# MCU_Power_PCB_Rev1.net
KiCad netlist of a schematic drawn in EAGLE
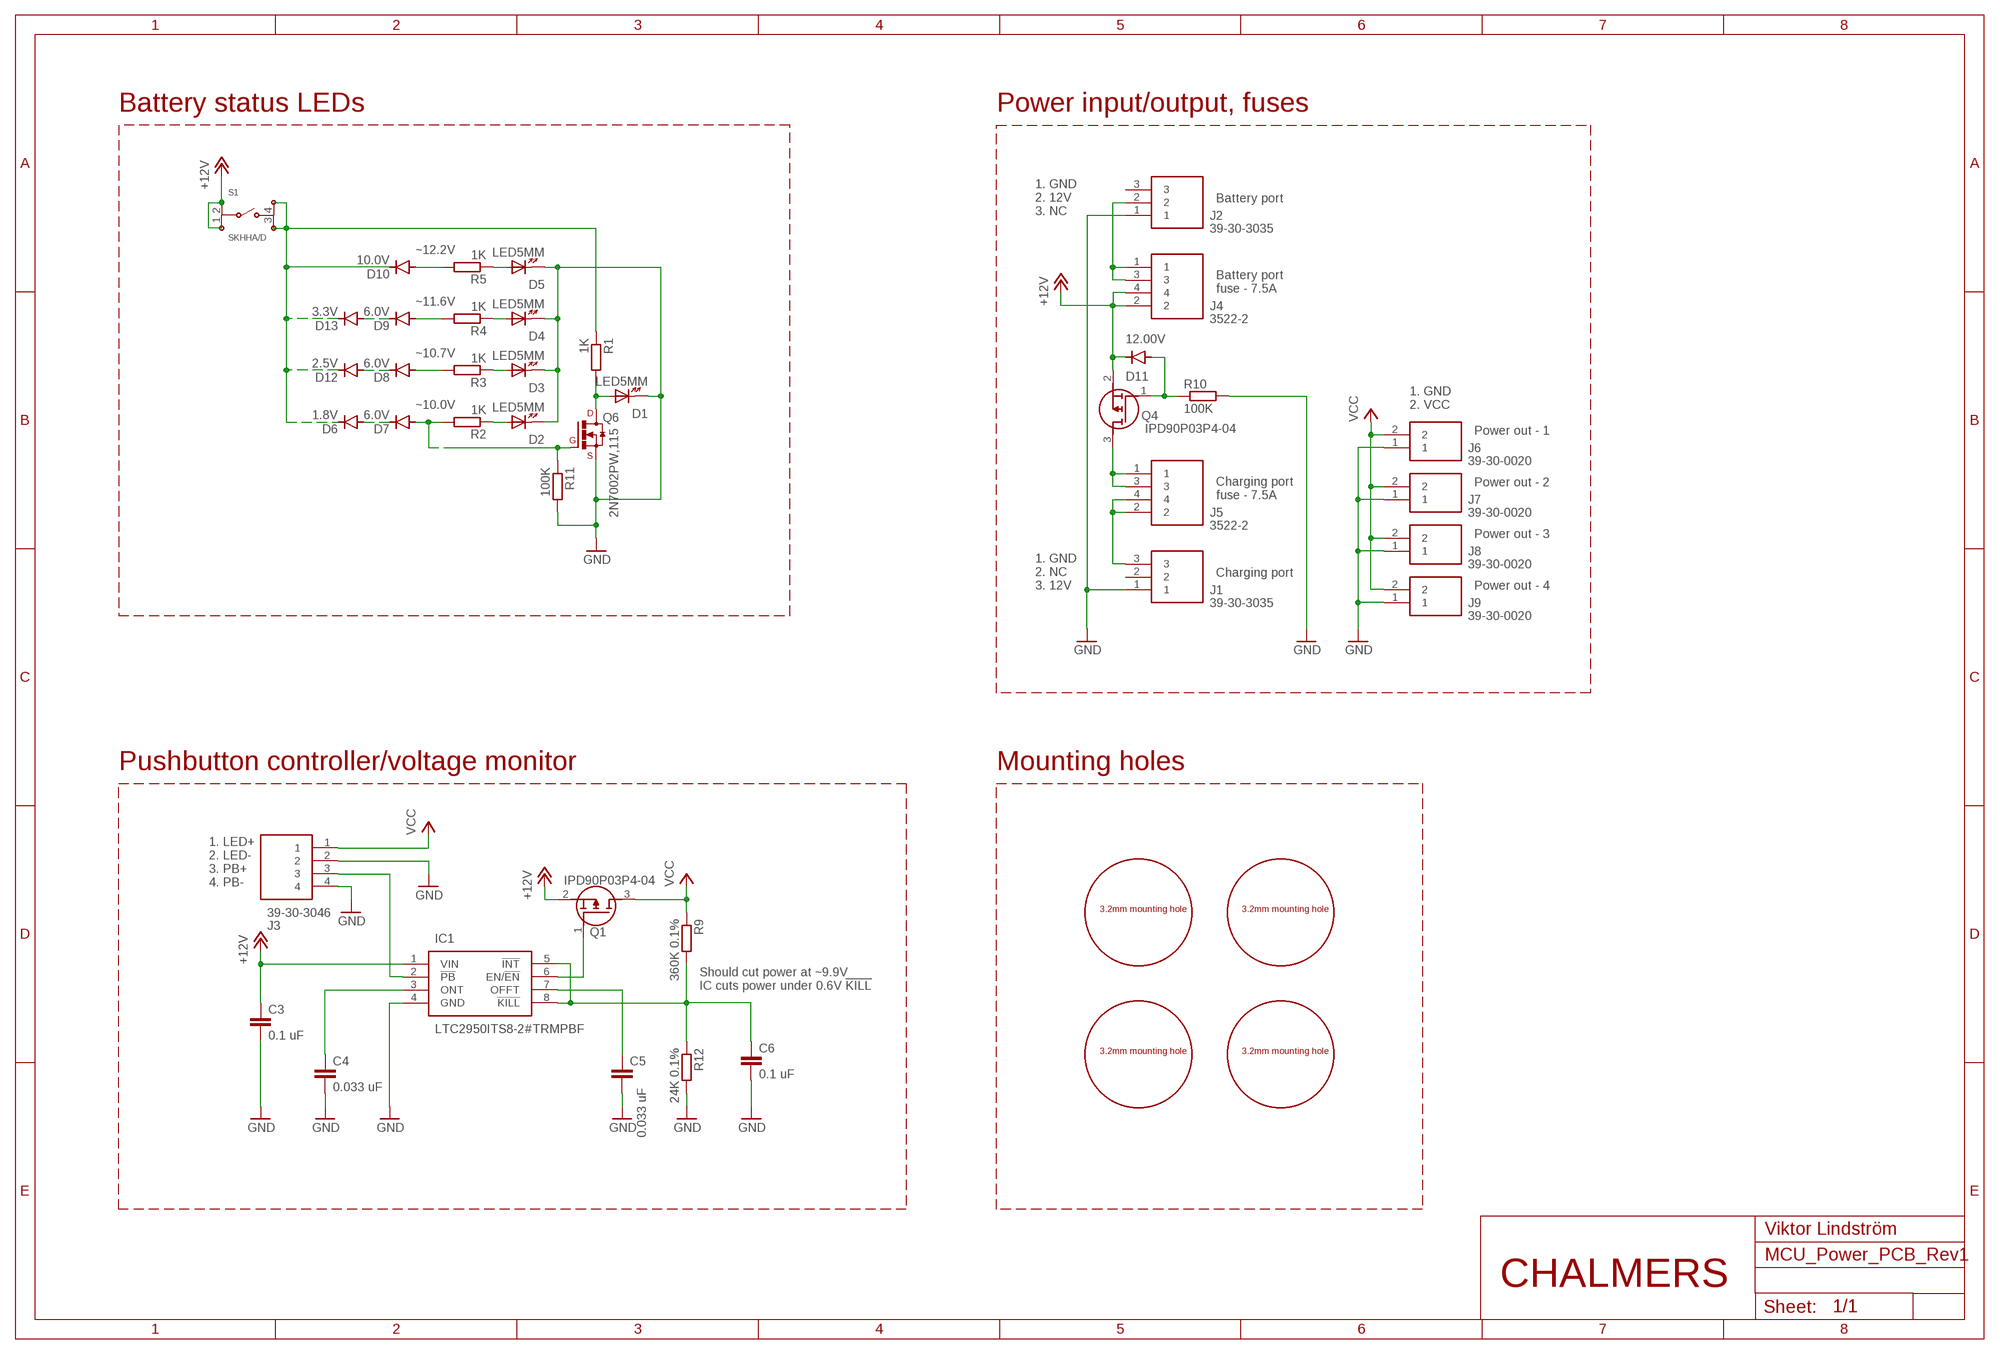
[diagram p0: schematic, sheet 1]

(export (version "E")
  (design (tool "Eeschema 10.0.6"))
  (components
    (comp (ref "C3")
      (value "0.1 uF")
      (footprint "eagle-import:C0603")
      (libsource (lib "eagle-import") (part "C0603"))
    )
    (comp (ref "C4")
      (value "0.033 uF")
      (footprint "eagle-import:C0603")
      (libsource (lib "eagle-import") (part "C0603"))
    )
    (comp (ref "C5")
      (value "0.033 uF")
      (footprint "eagle-import:C0603")
      (libsource (lib "eagle-import") (part "C0603"))
    )
    (comp (ref "C6")
      (value "0.1 uF")
      (footprint "eagle-import:C0603")
      (libsource (lib "eagle-import") (part "C0603"))
    )
    (comp (ref "D1")
      (value "LED5MM")
      (footprint "eagle-import:LED5MM")
      (libsource (lib "eagle-import") (part "LED5MM"))
    )
    (comp (ref "D2")
      (value "LED5MM")
      (footprint "eagle-import:LED5MM")
      (libsource (lib "eagle-import") (part "LED5MM"))
    )
    (comp (ref "D3")
      (value "LED5MM")
      (footprint "eagle-import:LED5MM")
      (libsource (lib "eagle-import") (part "LED5MM"))
    )
    (comp (ref "D4")
      (value "LED5MM")
      (footprint "eagle-import:LED5MM")
      (libsource (lib "eagle-import") (part "LED5MM"))
    )
    (comp (ref "D5")
      (value "LED5MM")
      (footprint "eagle-import:LED5MM")
      (libsource (lib "eagle-import") (part "LED5MM"))
    )
    (comp (ref "D6")
      (value "1.8V")
      (footprint "eagle-import:SOD-123_MINI-SMA")
      (libsource (lib "eagle-import") (part "CGRM400-G1"))
    )
    (comp (ref "D7")
      (value "6.0V")
      (footprint "eagle-import:SOD-123_MINI-SMA")
      (libsource (lib "eagle-import") (part "CGRM400-G1"))
    )
    (comp (ref "D8")
      (value "6.0V")
      (footprint "eagle-import:SOD-123_MINI-SMA")
      (libsource (lib "eagle-import") (part "CGRM400-G1"))
    )
    (comp (ref "D9")
      (value "6.0V")
      (footprint "eagle-import:SOD-123_MINI-SMA")
      (libsource (lib "eagle-import") (part "CGRM400-G1"))
    )
    (comp (ref "D10")
      (value "10.0V")
      (footprint "eagle-import:SOD-123_MINI-SMA")
      (libsource (lib "eagle-import") (part "CGRM400-G1"))
    )
    (comp (ref "D11")
      (value "12.00V")
      (footprint "eagle-import:SOD-123_MINI-SMA")
      (libsource (lib "eagle-import") (part "CGRM400-G1"))
    )
    (comp (ref "D12")
      (value "2.5V")
      (footprint "eagle-import:SOD-123_MINI-SMA")
      (libsource (lib "eagle-import") (part "CGRM400-G1"))
    )
    (comp (ref "D13")
      (value "3.3V")
      (footprint "eagle-import:SOD-123_MINI-SMA")
      (libsource (lib "eagle-import") (part "CGRM400-G1"))
    )
    (comp (ref "HOLE1")
      (value "M3_MOUNTING_HOLE")
      (footprint "eagle-import:M3_MOUNTING_HOLE")
      (libsource (lib "eagle-import") (part "M3_MOUNTING_HOLE"))
    )
    (comp (ref "HOLE2")
      (value "M3_MOUNTING_HOLE")
      (footprint "eagle-import:M3_MOUNTING_HOLE")
      (libsource (lib "eagle-import") (part "M3_MOUNTING_HOLE"))
    )
    (comp (ref "HOLE3")
      (value "M3_MOUNTING_HOLE")
      (footprint "eagle-import:M3_MOUNTING_HOLE")
      (libsource (lib "eagle-import") (part "M3_MOUNTING_HOLE"))
    )
    (comp (ref "HOLE4")
      (value "M3_MOUNTING_HOLE")
      (footprint "eagle-import:M3_MOUNTING_HOLE")
      (libsource (lib "eagle-import") (part "M3_MOUNTING_HOLE"))
    )
    (comp (ref "IC1")
      (value "LTC2950ITS8-2#TRMPBF")
      (footprint "eagle-import:SOT65P280X100-8N")
      (fields (field (name "RS_PART_NUMBER") "8225976P"))
      (libsource (lib "eagle-import") (part "LTC2950ITS8-2#TRMPBF"))
    )
    (comp (ref "J1")
      (value "39-30-3035")
      (footprint "eagle-import:39303035")
      (fields (field (name "RS_PART_NUMBER") "6705849P"))
      (libsource (lib "eagle-import") (part "39-30-3035"))
    )
    (comp (ref "J2")
      (value "39-30-3035")
      (footprint "eagle-import:39303035")
      (fields (field (name "RS_PART_NUMBER") "6705849P"))
      (libsource (lib "eagle-import") (part "39-30-3035"))
    )
    (comp (ref "J3")
      (value "39-30-3046")
      (footprint "eagle-import:39303046")
      (fields (field (name "RS_PART_NUMBER") "6705859P"))
      (libsource (lib "eagle-import") (part "39-30-3046"))
    )
    (comp (ref "J4")
      (value "3522-2")
      (footprint "eagle-import:35222")
      (fields (field (name "RS_PART_NUMBER") "1676068"))
      (libsource (lib "eagle-import") (part "3522-2"))
    )
    (comp (ref "J5")
      (value "3522-2")
      (footprint "eagle-import:35222")
      (fields (field (name "RS_PART_NUMBER") "1676068"))
      (libsource (lib "eagle-import") (part "3522-2"))
    )
    (comp (ref "J6")
      (value "39-30-0020")
      (footprint "eagle-import:39-30-1020_1")
      (fields (field (name "RS_PART_NUMBER") "6705708P"))
      (libsource (lib "eagle-import") (part "39-30-0020"))
    )
    (comp (ref "J7")
      (value "39-30-0020")
      (footprint "eagle-import:39-30-1020_1")
      (fields (field (name "RS_PART_NUMBER") "6705708P"))
      (libsource (lib "eagle-import") (part "39-30-0020"))
    )
    (comp (ref "J8")
      (value "39-30-0020")
      (footprint "eagle-import:39-30-1020_1")
      (fields (field (name "RS_PART_NUMBER") "6705708P"))
      (libsource (lib "eagle-import") (part "39-30-0020"))
    )
    (comp (ref "J9")
      (value "39-30-0020")
      (footprint "eagle-import:39-30-1020_1")
      (fields (field (name "RS_PART_NUMBER") "6705708P"))
      (libsource (lib "eagle-import") (part "39-30-0020"))
    )
    (comp (ref "Q1")
      (value "IPD90P03P4-04")
      (footprint "eagle-import:PG-TO252-3-11")
      (libsource (lib "eagle-import") (part "IPD90P03P4-04"))
    )
    (comp (ref "Q4")
      (value "IPD90P03P4-04")
      (footprint "eagle-import:PG-TO252-3-11")
      (libsource (lib "eagle-import") (part "IPD90P03P4-04"))
    )
    (comp (ref "Q6")
      (value "2N7002PW,115")
      (footprint "eagle-import:SOT323")
      (libsource (lib "eagle-import") (part "2N7002PW,115"))
    )
    (comp (ref "R1")
      (value "1K")
      (footprint "eagle-import:R0603")
      (libsource (lib "eagle-import") (part "R0603"))
    )
    (comp (ref "R2")
      (value "1K")
      (footprint "eagle-import:R0603")
      (libsource (lib "eagle-import") (part "R0603"))
    )
    (comp (ref "R3")
      (value "1K")
      (footprint "eagle-import:R0603")
      (libsource (lib "eagle-import") (part "R0603"))
    )
    (comp (ref "R4")
      (value "1K")
      (footprint "eagle-import:R0603")
      (libsource (lib "eagle-import") (part "R0603"))
    )
    (comp (ref "R5")
      (value "1K")
      (footprint "eagle-import:R0603")
      (libsource (lib "eagle-import") (part "R0603"))
    )
    (comp (ref "R9")
      (value "360K 0.1%")
      (footprint "eagle-import:R0603")
      (libsource (lib "eagle-import") (part "R0603"))
    )
    (comp (ref "R10")
      (value "100K")
      (footprint "eagle-import:R0603")
      (libsource (lib "eagle-import") (part "R0603"))
    )
    (comp (ref "R11")
      (value "100K")
      (footprint "eagle-import:R0603")
      (libsource (lib "eagle-import") (part "R0603"))
    )
    (comp (ref "R12")
      (value "24K 0.1%")
      (footprint "eagle-import:R0603")
      (libsource (lib "eagle-import") (part "R0603"))
    )
    (comp (ref "S1")
      (value "SKHHA/D")
      (footprint "eagle-import:SKHHA_D")
      (libsource (lib "eagle-import") (part "SKHHA/D"))
    )
  )
  (nets
    (net (code "1") (name "+12V") (class "Default")
      (node (ref "C3") (pin "1") (pinfunction "1_1") (pintype "passive"))
      (node (ref "D11") (pin "C") (pinfunction "C_C") (pintype "passive"))
      (node (ref "IC1") (pin "1") (pinfunction "VIN_1") (pintype "bidirectional"))
      (node (ref "J4") (pin "2") (pinfunction "2_2") (pintype "bidirectional"))
      (node (ref "J4") (pin "4") (pinfunction "4_4") (pintype "bidirectional"))
      (node (ref "Q1") (pin "2") (pinfunction "S_2") (pintype "bidirectional"))
      (node (ref "Q4") (pin "2") (pinfunction "S_2") (pintype "bidirectional"))
      (node (ref "S1") (pin "1") (pinfunction "1_1") (pintype "bidirectional"))
      (node (ref "S1") (pin "2") (pinfunction "2_2") (pintype "bidirectional"))
    )
    (net (code "2") (name "GND") (class "Default")
      (node (ref "C3") (pin "2") (pinfunction "2_2") (pintype "passive"))
      (node (ref "C4") (pin "2") (pinfunction "2_2") (pintype "passive"))
      (node (ref "C5") (pin "2") (pinfunction "2_2") (pintype "passive"))
      (node (ref "C6") (pin "2") (pinfunction "2_2") (pintype "passive"))
      (node (ref "D1") (pin "K") (pinfunction "K_K") (pintype "passive"))
      (node (ref "D2") (pin "K") (pinfunction "K_K") (pintype "passive"))
      (node (ref "D3") (pin "K") (pinfunction "K_K") (pintype "passive"))
      (node (ref "D4") (pin "K") (pinfunction "K_K") (pintype "passive"))
      (node (ref "D5") (pin "K") (pinfunction "K_K") (pintype "passive"))
      (node (ref "IC1") (pin "4") (pinfunction "GND_4") (pintype "bidirectional"))
      (node (ref "J1") (pin "1") (pinfunction "1_1") (pintype "bidirectional"))
      (node (ref "J2") (pin "1") (pinfunction "1_1") (pintype "bidirectional"))
      (node (ref "J3") (pin "2") (pinfunction "2_2") (pintype "bidirectional"))
      (node (ref "J3") (pin "4") (pinfunction "4_4") (pintype "bidirectional"))
      (node (ref "J6") (pin "1") (pinfunction "1_1") (pintype "bidirectional"))
      (node (ref "J7") (pin "1") (pinfunction "1_1") (pintype "bidirectional"))
      (node (ref "J8") (pin "1") (pinfunction "1_1") (pintype "bidirectional"))
      (node (ref "J9") (pin "1") (pinfunction "1_1") (pintype "bidirectional"))
      (node (ref "Q6") (pin "2") (pinfunction "S_2") (pintype "passive"))
      (node (ref "R10") (pin "2") (pinfunction "2_2") (pintype "passive"))
      (node (ref "R11") (pin "2") (pinfunction "2_2") (pintype "passive"))
      (node (ref "R12") (pin "2") (pinfunction "2_2") (pintype "passive"))
    )
    (net (code "3") (name "Net-(D2-PadA)") (class "Default")
      (node (ref "D2") (pin "A") (pinfunction "A_A") (pintype "passive"))
      (node (ref "R2") (pin "1") (pinfunction "1_1") (pintype "passive"))
    )
    (net (code "4") (name "Net-(D3-PadA)") (class "Default")
      (node (ref "D3") (pin "A") (pinfunction "A_A") (pintype "passive"))
      (node (ref "R3") (pin "1") (pinfunction "1_1") (pintype "passive"))
    )
    (net (code "5") (name "Net-(D4-PadA)") (class "Default")
      (node (ref "D4") (pin "A") (pinfunction "A_A") (pintype "passive"))
      (node (ref "R4") (pin "1") (pinfunction "1_1") (pintype "passive"))
    )
    (net (code "6") (name "Net-(D5-PadA)") (class "Default")
      (node (ref "D5") (pin "A") (pinfunction "A_A") (pintype "passive"))
      (node (ref "R5") (pin "1") (pinfunction "1_1") (pintype "passive"))
    )
    (net (code "7") (name "Net-(D6-PadA)") (class "Default")
      (node (ref "D6") (pin "A") (pinfunction "A_A") (pintype "passive"))
      (node (ref "D7") (pin "C") (pinfunction "C_C") (pintype "passive"))
    )
    (net (code "8") (name "Net-(D8-PadA)") (class "Default")
      (node (ref "D8") (pin "A") (pinfunction "A_A") (pintype "passive"))
      (node (ref "R3") (pin "2") (pinfunction "2_2") (pintype "passive"))
    )
    (net (code "9") (name "Net-(D9-PadA)") (class "Default")
      (node (ref "D9") (pin "A") (pinfunction "A_A") (pintype "passive"))
      (node (ref "R4") (pin "2") (pinfunction "2_2") (pintype "passive"))
    )
    (net (code "10") (name "Net-(D10-PadA)") (class "Default")
      (node (ref "D10") (pin "A") (pinfunction "A_A") (pintype "passive"))
      (node (ref "R5") (pin "2") (pinfunction "2_2") (pintype "passive"))
    )
    (net (code "11") (name "Net-(D10-PadC)") (class "Default")
      (node (ref "D10") (pin "C") (pinfunction "C_C") (pintype "passive"))
      (node (ref "D12") (pin "C") (pinfunction "C_C") (pintype "passive"))
      (node (ref "D13") (pin "C") (pinfunction "C_C") (pintype "passive"))
      (node (ref "D6") (pin "C") (pinfunction "C_C") (pintype "passive"))
      (node (ref "R1") (pin "1") (pinfunction "1_1") (pintype "passive"))
      (node (ref "S1") (pin "3") (pinfunction "3_3") (pintype "bidirectional"))
      (node (ref "S1") (pin "4") (pinfunction "4_4") (pintype "bidirectional"))
    )
    (net (code "12") (name "Net-(D12-PadA)") (class "Default")
      (node (ref "D12") (pin "A") (pinfunction "A_A") (pintype "passive"))
      (node (ref "D8") (pin "C") (pinfunction "C_C") (pintype "passive"))
    )
    (net (code "13") (name "Net-(D13-PadA)") (class "Default")
      (node (ref "D13") (pin "A") (pinfunction "A_A") (pintype "passive"))
      (node (ref "D9") (pin "C") (pinfunction "C_C") (pintype "passive"))
    )
    (net (code "14") (name "Net-(IC1-EN{slash}~{EN})") (class "Default")
      (node (ref "IC1") (pin "6") (pinfunction "EN/~{EN}_6") (pintype "bidirectional"))
      (node (ref "Q1") (pin "1") (pinfunction "G_1") (pintype "bidirectional"))
    )
    (net (code "15") (name "Net-(IC1-OFFT)") (class "Default")
      (node (ref "C5") (pin "1") (pinfunction "1_1") (pintype "passive"))
      (node (ref "IC1") (pin "7") (pinfunction "OFFT_7") (pintype "bidirectional"))
    )
    (net (code "16") (name "Net-(IC1-ONT)") (class "Default")
      (node (ref "C4") (pin "1") (pinfunction "1_1") (pintype "passive"))
      (node (ref "IC1") (pin "3") (pinfunction "ONT_3") (pintype "bidirectional"))
    )
    (net (code "17") (name "Net-(IC1-~{INT})") (class "Default")
      (node (ref "C6") (pin "1") (pinfunction "1_1") (pintype "passive"))
      (node (ref "IC1") (pin "5") (pinfunction "~{INT}_5") (pintype "bidirectional"))
      (node (ref "IC1") (pin "8") (pinfunction "~{KILL}_8") (pintype "bidirectional"))
      (node (ref "R12") (pin "1") (pinfunction "1_1") (pintype "passive"))
      (node (ref "R9") (pin "2") (pinfunction "2_2") (pintype "passive"))
    )
    (net (code "18") (name "Net-(IC1-~{PB})") (class "Default")
      (node (ref "IC1") (pin "2") (pinfunction "~{PB}_2") (pintype "bidirectional"))
      (node (ref "J3") (pin "3") (pinfunction "3_3") (pintype "bidirectional"))
    )
    (net (code "19") (name "Net-(J1-Pad3)") (class "Default")
      (node (ref "J1") (pin "3") (pinfunction "3_3") (pintype "bidirectional"))
      (node (ref "J5") (pin "2") (pinfunction "2_2") (pintype "bidirectional"))
      (node (ref "J5") (pin "4") (pinfunction "4_4") (pintype "bidirectional"))
    )
    (net (code "20") (name "Net-(J2-Pad2)") (class "Default")
      (node (ref "J2") (pin "2") (pinfunction "2_2") (pintype "bidirectional"))
      (node (ref "J4") (pin "1") (pinfunction "1_1") (pintype "bidirectional"))
      (node (ref "J4") (pin "3") (pinfunction "3_3") (pintype "bidirectional"))
    )
    (net (code "21") (name "Net-(Q4-D)") (class "Default")
      (node (ref "J5") (pin "1") (pinfunction "1_1") (pintype "bidirectional"))
      (node (ref "J5") (pin "3") (pinfunction "3_3") (pintype "bidirectional"))
      (node (ref "Q4") (pin "3") (pinfunction "D_3") (pintype "bidirectional"))
    )
    (net (code "22") (name "Net-(Q4-G)") (class "Default")
      (node (ref "D11") (pin "A") (pinfunction "A_A") (pintype "passive"))
      (node (ref "Q4") (pin "1") (pinfunction "G_1") (pintype "bidirectional"))
      (node (ref "R10") (pin "1") (pinfunction "1_1") (pintype "passive"))
    )
    (net (code "23") (name "Net-(Q6-D)") (class "Default")
      (node (ref "D1") (pin "A") (pinfunction "A_A") (pintype "passive"))
      (node (ref "Q6") (pin "3") (pinfunction "D_3") (pintype "passive"))
      (node (ref "R1") (pin "2") (pinfunction "2_2") (pintype "passive"))
    )
    (net (code "24") (name "Net-(Q6-G)") (class "Default")
      (node (ref "D7") (pin "A") (pinfunction "A_A") (pintype "passive"))
      (node (ref "Q6") (pin "1") (pinfunction "G_1") (pintype "passive"))
      (node (ref "R11") (pin "1") (pinfunction "1_1") (pintype "passive"))
      (node (ref "R2") (pin "2") (pinfunction "2_2") (pintype "passive"))
    )
    (net (code "25") (name "VCC") (class "Default")
      (node (ref "J3") (pin "1") (pinfunction "1_1") (pintype "bidirectional"))
      (node (ref "J6") (pin "2") (pinfunction "2_2") (pintype "bidirectional"))
      (node (ref "J7") (pin "2") (pinfunction "2_2") (pintype "bidirectional"))
      (node (ref "J8") (pin "2") (pinfunction "2_2") (pintype "bidirectional"))
      (node (ref "J9") (pin "2") (pinfunction "2_2") (pintype "bidirectional"))
      (node (ref "Q1") (pin "3") (pinfunction "D_3") (pintype "bidirectional"))
      (node (ref "R9") (pin "1") (pinfunction "1_1") (pintype "passive"))
    )
    (net (code "26") (name "unconnected-(J1-Pad2)") (class "Default")
      (node (ref "J1") (pin "2") (pinfunction "2_2") (pintype "bidirectional"))
    )
    (net (code "27") (name "unconnected-(J2-Pad3)") (class "Default")
      (node (ref "J2") (pin "3") (pinfunction "3_3") (pintype "bidirectional"))
    )
  )
)
